# avr_sample_hx711.net
KiCad netlist of a schematic drawn in EAGLE
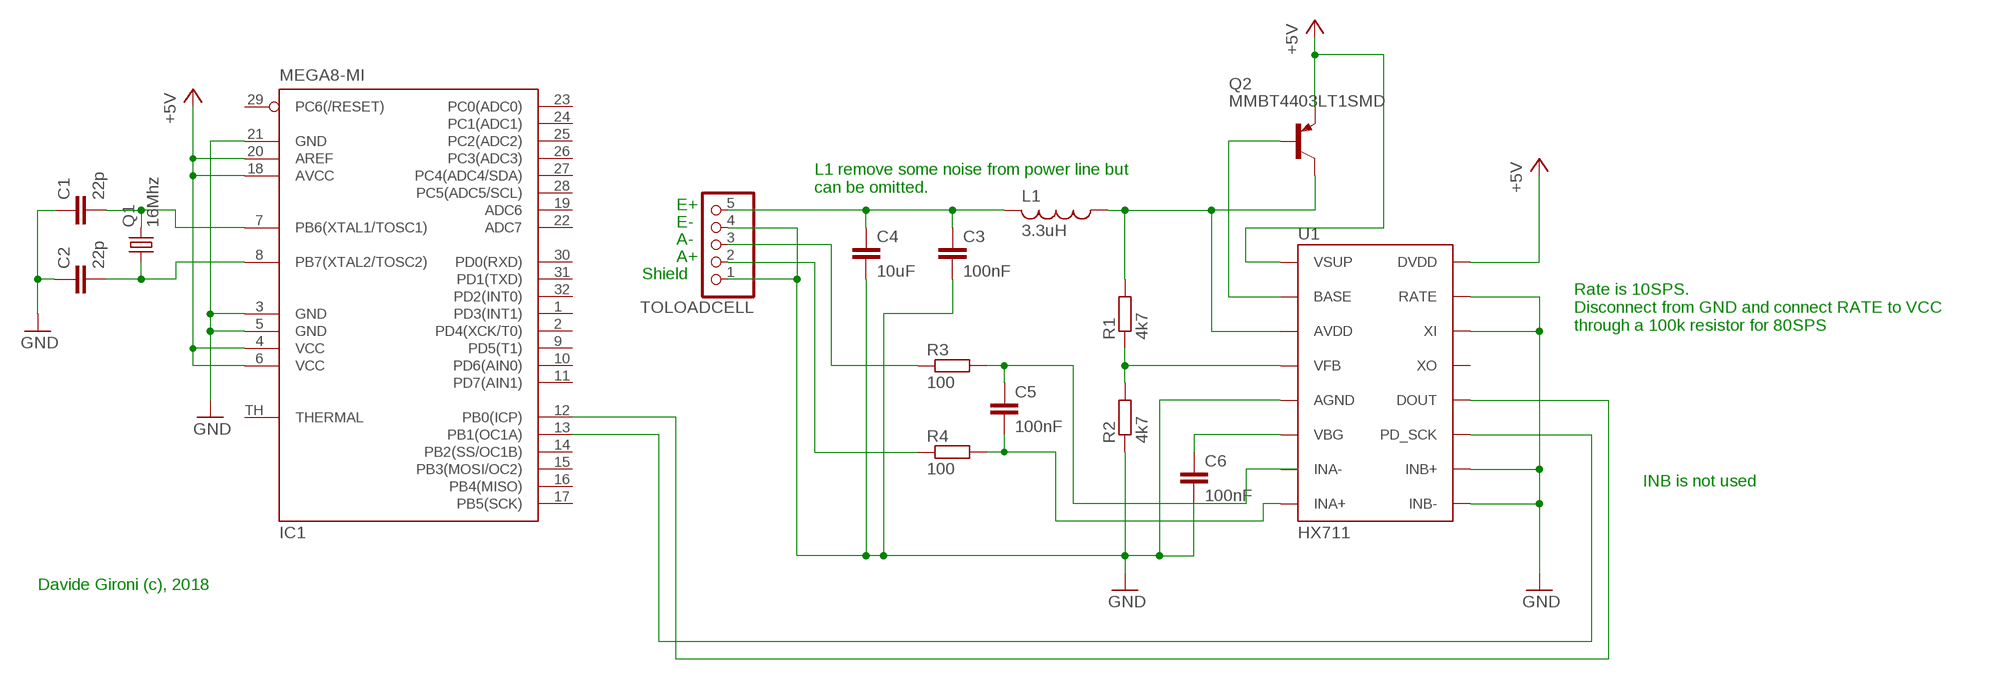
[diagram p0: schematic, sheet 1]

(export (version "E")
  (design (tool "Eeschema 10.0.6"))
  (components
    (comp (ref "C1")
      (value "22p")
      (footprint "eagle-import:C0805")
      (libsource (lib "eagle-import") (part "C-EUC0805"))
    )
    (comp (ref "C2")
      (value "22p")
      (footprint "eagle-import:C0805")
      (libsource (lib "eagle-import") (part "C-EUC0805"))
    )
    (comp (ref "C3")
      (value "100nF")
      (footprint "eagle-import:C0805")
      (libsource (lib "eagle-import") (part "C-EUC0805"))
    )
    (comp (ref "C4")
      (value "10uF")
      (footprint "eagle-import:C0805")
      (libsource (lib "eagle-import") (part "C-EUC0805"))
    )
    (comp (ref "C5")
      (value "100nF")
      (footprint "eagle-import:C0805")
      (libsource (lib "eagle-import") (part "C-EUC0805"))
    )
    (comp (ref "C6")
      (value "100nF")
      (footprint "eagle-import:C0805")
      (libsource (lib "eagle-import") (part "C-EUC0805"))
    )
    (comp (ref "IC1")
      (value "MEGA8-MI")
      (footprint "eagle-import:MLF32-TH")
      (fields (field (name "MPN") "ATMEGA88PA-MU"))
      (libsource (lib "eagle-import") (part "MEGA8-MI"))
    )
    (comp (ref "L1")
      (value "3.3uH")
      (footprint "eagle-import:L4532M")
      (libsource (lib "eagle-import") (part "L-USL4532C"))
    )
    (comp (ref "Q1")
      (value "16Mhz")
      (footprint "eagle-import:HC33U-V")
      (libsource (lib "eagle-import") (part "CRYSTALHC33U-V"))
    )
    (comp (ref "Q2")
      (value "MMBT4403LT1SMD")
      (footprint "eagle-import:SOT23-BEC")
      (libsource (lib "eagle-import") (part "MMBT4403SMDLT1"))
    )
    (comp (ref "R1")
      (value "4k7")
      (footprint "eagle-import:R0603")
      (libsource (lib "eagle-import") (part "R-EU_R0603"))
    )
    (comp (ref "R2")
      (value "4k7")
      (footprint "eagle-import:R0603")
      (libsource (lib "eagle-import") (part "R-EU_R0603"))
    )
    (comp (ref "R3")
      (value "100")
      (footprint "eagle-import:R0603")
      (libsource (lib "eagle-import") (part "R-EU_R0603"))
    )
    (comp (ref "R4")
      (value "100")
      (footprint "eagle-import:R0603")
      (libsource (lib "eagle-import") (part "R-EU_R0603"))
    )
    (comp (ref "TOLOADCELL")
      (value "PINHD-1X5")
      (footprint "eagle-import:1X05")
      (libsource (lib "eagle-import") (part "PINHD-1X5"))
    )
    (comp (ref "U1")
      (value "HX711")
      (footprint "eagle-import:SO16")
      (libsource (lib "eagle-import") (part "HX711HX711"))
    )
  )
  (nets
    (net (code "1") (name "+5V") (class "Default")
      (node (ref "IC1") (pin "18") (pinfunction "AVCC_18") (pintype "power_in"))
      (node (ref "IC1") (pin "20") (pinfunction "AREF_20") (pintype "passive"))
      (node (ref "IC1") (pin "4") (pinfunction "VCC_4") (pintype "power_in"))
      (node (ref "IC1") (pin "6") (pinfunction "VCC_6") (pintype "power_in"))
      (node (ref "Q2") (pin "E") (pinfunction "E_E") (pintype "passive"))
      (node (ref "U1") (pin "1") (pinfunction "VSUP_1") (pintype "bidirectional"))
      (node (ref "U1") (pin "16") (pinfunction "DVDD_16") (pintype "bidirectional"))
    )
    (net (code "2") (name "GND") (class "Default")
      (node (ref "C1") (pin "1") (pinfunction "1_1") (pintype "passive"))
      (node (ref "C2") (pin "1") (pinfunction "1_1") (pintype "passive"))
      (node (ref "C3") (pin "2") (pinfunction "2_2") (pintype "passive"))
      (node (ref "C4") (pin "2") (pinfunction "2_2") (pintype "passive"))
      (node (ref "C6") (pin "2") (pinfunction "2_2") (pintype "passive"))
      (node (ref "IC1") (pin "21") (pinfunction "GND_21") (pintype "power_in"))
      (node (ref "IC1") (pin "3") (pinfunction "GND_3") (pintype "power_in"))
      (node (ref "IC1") (pin "5") (pinfunction "GND_5") (pintype "power_in"))
      (node (ref "R2") (pin "1") (pinfunction "1_1") (pintype "passive"))
      (node (ref "TOLOADCELL") (pin "1") (pinfunction "1_1") (pintype "passive"))
      (node (ref "TOLOADCELL") (pin "4") (pinfunction "4_4") (pintype "passive"))
      (node (ref "U1") (pin "10") (pinfunction "INB+_10") (pintype "bidirectional"))
      (node (ref "U1") (pin "14") (pinfunction "XI_14") (pintype "bidirectional"))
      (node (ref "U1") (pin "15") (pinfunction "RATE_15") (pintype "bidirectional"))
      (node (ref "U1") (pin "5") (pinfunction "AGND_5") (pintype "bidirectional"))
      (node (ref "U1") (pin "9") (pinfunction "INB-_9") (pintype "bidirectional"))
    )
    (net (code "3") (name "Net-(C3-Pad1)") (class "Default")
      (node (ref "C3") (pin "1") (pinfunction "1_1") (pintype "passive"))
      (node (ref "C4") (pin "1") (pinfunction "1_1") (pintype "passive"))
      (node (ref "L1") (pin "2") (pinfunction "2_2") (pintype "passive"))
      (node (ref "TOLOADCELL") (pin "5") (pinfunction "5_5") (pintype "passive"))
    )
    (net (code "4") (name "Net-(C5-Pad1)") (class "Default")
      (node (ref "C5") (pin "1") (pinfunction "1_1") (pintype "passive"))
      (node (ref "R3") (pin "2") (pinfunction "2_2") (pintype "passive"))
    )
    (net (code "5") (name "Net-(IC1-PB0(ICP))") (class "Default")
      (node (ref "IC1") (pin "12") (pinfunction "PB0(ICP)_12") (pintype "bidirectional"))
      (node (ref "U1") (pin "12") (pinfunction "DOUT_12") (pintype "bidirectional"))
    )
    (net (code "6") (name "Net-(IC1-PB1(OC1A))") (class "Default")
      (node (ref "IC1") (pin "13") (pinfunction "PB1(OC1A)_13") (pintype "bidirectional"))
      (node (ref "U1") (pin "11") (pinfunction "PD_SCK_11") (pintype "bidirectional"))
    )
    (net (code "7") (name "Net-(IC1-PB6(XTAL1{slash}TOSC1))") (class "Default")
      (node (ref "C1") (pin "2") (pinfunction "2_2") (pintype "passive"))
      (node (ref "IC1") (pin "7") (pinfunction "PB6(XTAL1/TOSC1)_7") (pintype "bidirectional"))
      (node (ref "Q1") (pin "2") (pinfunction "2_2") (pintype "passive"))
    )
    (net (code "8") (name "Net-(IC1-PB7(XTAL2{slash}TOSC2))") (class "Default")
      (node (ref "C2") (pin "2") (pinfunction "2_2") (pintype "passive"))
      (node (ref "IC1") (pin "8") (pinfunction "PB7(XTAL2/TOSC2)_8") (pintype "bidirectional"))
      (node (ref "Q1") (pin "1") (pinfunction "1_1") (pintype "passive"))
    )
    (net (code "9") (name "Net-(R3-Pad1)") (class "Default")
      (node (ref "R3") (pin "1") (pinfunction "1_1") (pintype "passive"))
      (node (ref "TOLOADCELL") (pin "3") (pinfunction "3_3") (pintype "passive"))
    )
    (net (code "10") (name "Net-(R4-Pad1)") (class "Default")
      (node (ref "R4") (pin "1") (pinfunction "1_1") (pintype "passive"))
      (node (ref "TOLOADCELL") (pin "2") (pinfunction "2_2") (pintype "passive"))
    )
    (net (code "11") (name "Net-(U1-AVDD)") (class "Default")
      (node (ref "L1") (pin "1") (pinfunction "1_1") (pintype "passive"))
      (node (ref "Q2") (pin "C") (pinfunction "C_C") (pintype "passive"))
      (node (ref "R1") (pin "2") (pinfunction "2_2") (pintype "passive"))
      (node (ref "U1") (pin "3") (pinfunction "AVDD_3") (pintype "bidirectional"))
    )
    (net (code "12") (name "Net-(U1-BASE)") (class "Default")
      (node (ref "Q2") (pin "B") (pinfunction "B_B") (pintype "passive"))
      (node (ref "U1") (pin "2") (pinfunction "BASE_2") (pintype "bidirectional"))
    )
    (net (code "13") (name "Net-(U1-INA+)") (class "Default")
      (node (ref "C5") (pin "2") (pinfunction "2_2") (pintype "passive"))
      (node (ref "R4") (pin "2") (pinfunction "2_2") (pintype "passive"))
      (node (ref "U1") (pin "8") (pinfunction "INA+_8") (pintype "bidirectional"))
    )
    (net (code "14") (name "Net-(U1-VBG)") (class "Default")
      (node (ref "C6") (pin "1") (pinfunction "1_1") (pintype "passive"))
      (node (ref "U1") (pin "6") (pinfunction "VBG_6") (pintype "bidirectional"))
    )
    (net (code "15") (name "Net-(U1-VFB)") (class "Default")
      (node (ref "R1") (pin "1") (pinfunction "1_1") (pintype "passive"))
      (node (ref "R2") (pin "2") (pinfunction "2_2") (pintype "passive"))
      (node (ref "U1") (pin "4") (pinfunction "VFB_4") (pintype "bidirectional"))
    )
    (net (code "16") (name "unconnected-(IC1-ADC6-Pad19)") (class "Default")
      (node (ref "IC1") (pin "19") (pinfunction "ADC6_19") (pintype "bidirectional"))
    )
    (net (code "17") (name "unconnected-(IC1-ADC7-Pad22)") (class "Default")
      (node (ref "IC1") (pin "22") (pinfunction "ADC7_22") (pintype "bidirectional"))
    )
    (net (code "18") (name "unconnected-(IC1-PB2(SS{slash}OC1B)-Pad14)") (class "Default")
      (node (ref "IC1") (pin "14") (pinfunction "PB2(SS/OC1B)_14") (pintype "bidirectional"))
    )
    (net (code "19") (name "unconnected-(IC1-PB3(MOSI{slash}OC2)-Pad15)") (class "Default")
      (node (ref "IC1") (pin "15") (pinfunction "PB3(MOSI/OC2)_15") (pintype "bidirectional"))
    )
    (net (code "20") (name "unconnected-(IC1-PB4(MISO)-Pad16)") (class "Default")
      (node (ref "IC1") (pin "16") (pinfunction "PB4(MISO)_16") (pintype "bidirectional"))
    )
    (net (code "21") (name "unconnected-(IC1-PB5(SCK)-Pad17)") (class "Default")
      (node (ref "IC1") (pin "17") (pinfunction "PB5(SCK)_17") (pintype "bidirectional"))
    )
    (net (code "22") (name "unconnected-(IC1-PC0(ADC0)-Pad23)") (class "Default")
      (node (ref "IC1") (pin "23") (pinfunction "PC0(ADC0)_23") (pintype "bidirectional"))
    )
    (net (code "23") (name "unconnected-(IC1-PC1(ADC1)-Pad24)") (class "Default")
      (node (ref "IC1") (pin "24") (pinfunction "PC1(ADC1)_24") (pintype "bidirectional"))
    )
    (net (code "24") (name "unconnected-(IC1-PC2(ADC2)-Pad25)") (class "Default")
      (node (ref "IC1") (pin "25") (pinfunction "PC2(ADC2)_25") (pintype "bidirectional"))
    )
    (net (code "25") (name "unconnected-(IC1-PC3(ADC3)-Pad26)") (class "Default")
      (node (ref "IC1") (pin "26") (pinfunction "PC3(ADC3)_26") (pintype "bidirectional"))
    )
    (net (code "26") (name "unconnected-(IC1-PC4(ADC4{slash}SDA)-Pad27)") (class "Default")
      (node (ref "IC1") (pin "27") (pinfunction "PC4(ADC4/SDA)_27") (pintype "bidirectional"))
    )
    (net (code "27") (name "unconnected-(IC1-PC5(ADC5{slash}SCL)-Pad28)") (class "Default")
      (node (ref "IC1") (pin "28") (pinfunction "PC5(ADC5/SCL)_28") (pintype "bidirectional"))
    )
    (net (code "28") (name "unconnected-(IC1-PC6({slash}RESET)-Pad29)") (class "Default")
      (node (ref "IC1") (pin "29") (pinfunction "PC6(/RESET)_29") (pintype "bidirectional"))
    )
    (net (code "29") (name "unconnected-(IC1-PD0(RXD)-Pad30)") (class "Default")
      (node (ref "IC1") (pin "30") (pinfunction "PD0(RXD)_30") (pintype "bidirectional"))
    )
    (net (code "30") (name "unconnected-(IC1-PD1(TXD)-Pad31)") (class "Default")
      (node (ref "IC1") (pin "31") (pinfunction "PD1(TXD)_31") (pintype "bidirectional"))
    )
    (net (code "31") (name "unconnected-(IC1-PD2(INT0)-Pad32)") (class "Default")
      (node (ref "IC1") (pin "32") (pinfunction "PD2(INT0)_32") (pintype "bidirectional"))
    )
    (net (code "32") (name "unconnected-(IC1-PD3(INT1)-Pad1)") (class "Default")
      (node (ref "IC1") (pin "1") (pinfunction "PD3(INT1)_1") (pintype "bidirectional"))
    )
    (net (code "33") (name "unconnected-(IC1-PD4(XCK{slash}T0)-Pad2)") (class "Default")
      (node (ref "IC1") (pin "2") (pinfunction "PD4(XCK/T0)_2") (pintype "bidirectional"))
    )
    (net (code "34") (name "unconnected-(IC1-PD5(T1)-Pad9)") (class "Default")
      (node (ref "IC1") (pin "9") (pinfunction "PD5(T1)_9") (pintype "bidirectional"))
    )
    (net (code "35") (name "unconnected-(IC1-PD6(AIN0)-Pad10)") (class "Default")
      (node (ref "IC1") (pin "10") (pinfunction "PD6(AIN0)_10") (pintype "bidirectional"))
    )
    (net (code "36") (name "unconnected-(IC1-PD7(AIN1)-Pad11)") (class "Default")
      (node (ref "IC1") (pin "11") (pinfunction "PD7(AIN1)_11") (pintype "bidirectional"))
    )
    (net (code "37") (name "unconnected-(IC1-THERMAL-PadTH)") (class "Default")
      (node (ref "IC1") (pin "TH") (pinfunction "THERMAL_TH") (pintype "passive"))
    )
    (net (code "38") (name "unconnected-(U1-INA--Pad7)") (class "Default")
      (node (ref "U1") (pin "7") (pinfunction "INA-_7") (pintype "bidirectional"))
    )
    (net (code "39") (name "unconnected-(U1-XO-Pad13)") (class "Default")
      (node (ref "U1") (pin "13") (pinfunction "XO_13") (pintype "bidirectional"))
    )
  )
)
